# RTC_I2C_DS1338Z-3.net
KiCad netlist of a schematic drawn in Altium Designer
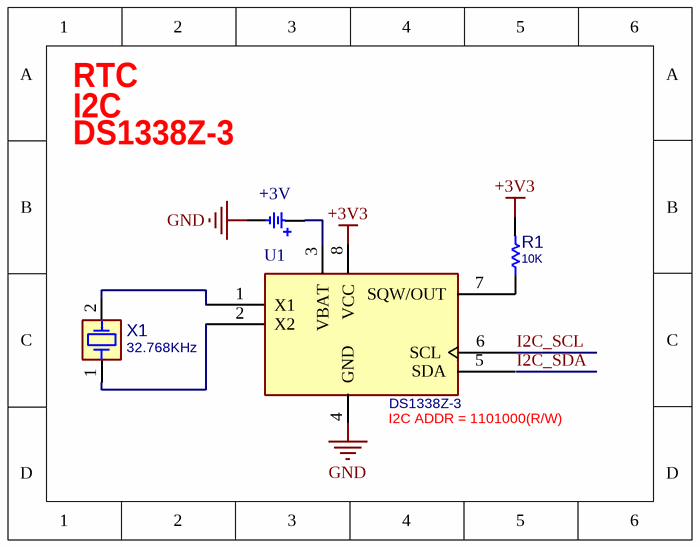
[diagram p0: RTC I2C DS1338Z-3.SchDoc]

(export (version "E")
  (design (tool "Eeschema 10.0.6"))
  (components
    (comp (ref "BT1")
      (value "+3V")
      (footprint "BTH1220")
      (description "BATTERY HOLDER, CR1220")
      (libsource (lib "PW Components") (part "BATH_CR1220"))
    )
    (comp (ref "R1")
      (value "10K")
      (footprint "R0603S")
      (description "RES, SMD")
      (fields (field (name "MANF_P#") "RK73H1ETTP4701F") (field (name "MANF") "KOA SPEER"))
      (libsource (lib "Passive") (part "RES_SMD"))
    )
    (comp (ref "U1")
      (value "DS1338")
      (footprint "SO_8")
      (description "Real-Time Clock, I2C")
      (fields (field (name "MANF") "Maxim Integrated") (field (name "MANF_P#") "DS1338Z-3+"))
      (libsource (lib "PW Components") (part "RTC_I2C_DS1338Z-3_SOP8"))
    )
    (comp (ref "X1")
      (value "32.768KHz")
      (footprint "XTL_2_3215")
      (description "32.768KHz SMT 3.2x1.5 FC-135R")
      (fields (field (name "MANF") "DIODES") (field (name "MANF_P#") "FL400WFQA1"))
      (libsource (lib "PW Components") (part "XTL_32.768KHz"))
    )
  )
  (nets
    (net (code "1") (name "+3V3") (class "Default")
      (node (ref "R1") (pin "2") (pinfunction "2_2") (pintype "passive"))
      (node (ref "U1") (pin "8") (pinfunction "VCC_8") (pintype "passive"))
    )
    (net (code "2") (name "/I2C_SCL") (class "Default")
      (node (ref "U1") (pin "6") (pinfunction "SCL_6") (pintype "passive"))
    )
    (net (code "4") (name "GND") (class "Default")
      (node (ref "BT1") (pin "2") (pinfunction "2_2") (pintype "passive"))
      (node (ref "U1") (pin "4") (pinfunction "GND_4") (pintype "passive"))
    )
    (net (code "5") (name "Net-(U1-SQW{slash}OUT)") (class "Default")
      (node (ref "R1") (pin "1") (pinfunction "1_1") (pintype "passive"))
      (node (ref "U1") (pin "7") (pinfunction "SQW/OUT_7") (pintype "passive"))
    )
    (net (code "6") (name "Net-(U1-VBAT)") (class "Default")
      (node (ref "BT1") (pin "1") (pinfunction "1_1") (pintype "passive"))
      (node (ref "U1") (pin "3") (pinfunction "VBAT_3") (pintype "passive"))
    )
    (net (code "7") (name "Net-(U1-X1)") (class "Default")
      (node (ref "U1") (pin "1") (pinfunction "X1_1") (pintype "passive"))
      (node (ref "X1") (pin "2") (pinfunction "2_2") (pintype "passive"))
    )
    (net (code "8") (name "Net-(U1-X2)") (class "Default")
      (node (ref "U1") (pin "2") (pinfunction "X2_2") (pintype "passive"))
      (node (ref "X1") (pin "1") (pinfunction "1_1") (pintype "passive"))
    )
    (net (code "9") (name "unconnected-(U1-SDA-Pad5)") (class "Default")
      (node (ref "U1") (pin "5") (pinfunction "SDA_5") (pintype "passive"))
    )
  )
)
